# 02-USER_IO.net
KiCad netlist of a schematic drawn in Altium Designer
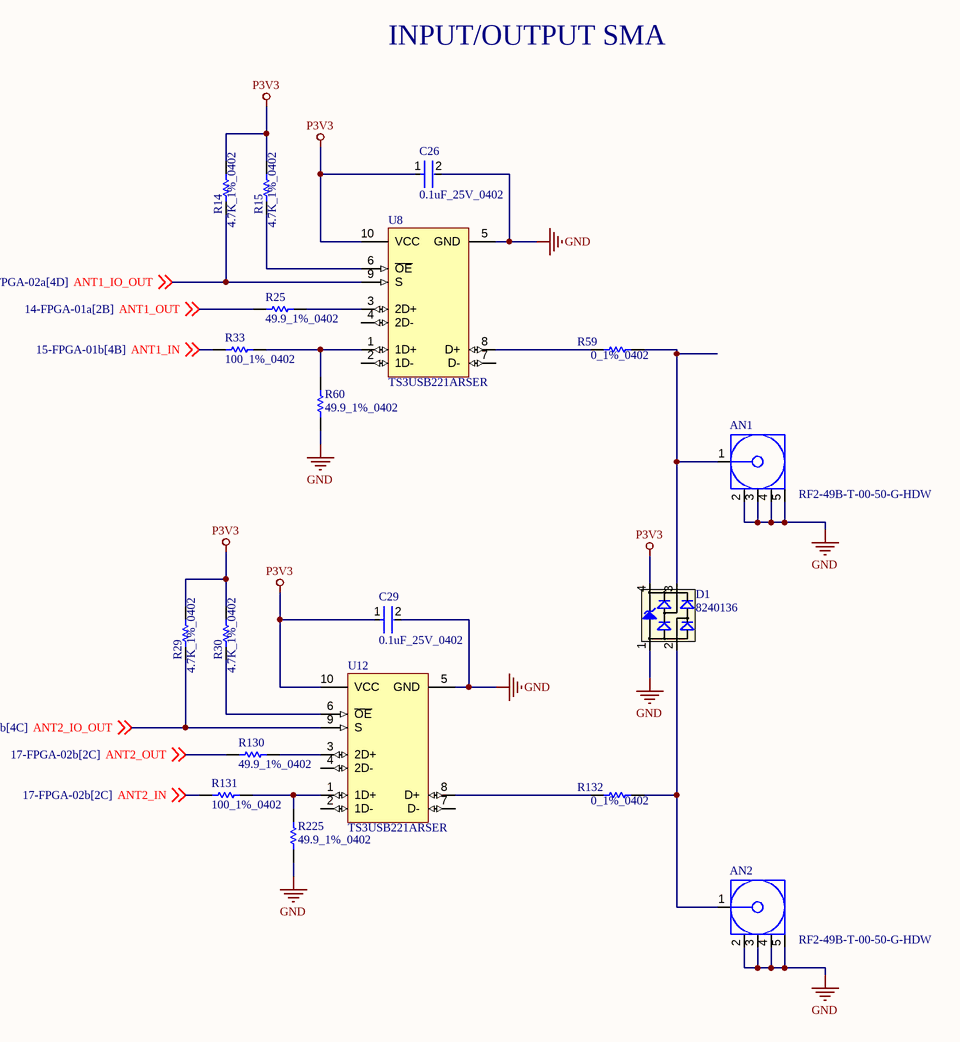
[diagram p0: 02-USER_IO.SchDoc]

(export (version "E")
  (design (tool "Eeschema 10.0.6"))
  (components
    (comp (ref "AN1")
      (value "RF2-49B-T-00-50-G-HDW")
      (footprint "AMPH-901-143-6RFX_V")
      (description "Coaxial connector, 50 Ohm, -65 to 165 degC, 5-Pin THD, RoHS, Bulk")
      (fields (field (name "MANUFACTURER") "Amphenol"))
      (libsource (lib "Altium Content Vault") (part "CN-S-4F-RF5"))
    )
    (comp (ref "AN2")
      (value "RF2-49B-T-00-50-G-HDW")
      (footprint "AMPH-901-143-6RFX_V")
      (description "Coaxial connector, 50 Ohm, -65 to 165 degC, 5-Pin THD, RoHS, Bulk")
      (fields (field (name "MANUFACTURER") "Amphenol"))
      (libsource (lib "Altium Content Vault") (part "CN-S-4F-RF5"))
    )
    (comp (ref "C26")
      (value "0.1uF_25V_0402")
      (footprint "FP-0402-L_1_0_1-W_0_5_0_1-IPC_C")
      (description "General Purpose Ceramic Capacitor, 0402, 100nF, 10%, X7R, 15%, 25V")
      (fields (field (name "VOLTAGE") "25V") (field (name "TOLERANCE") "10%"))
      (libsource (lib "Altium Content Vault") (part "b4654b650e69147ec39a6b967a45e02"))
    )
    (comp (ref "C29")
      (value "0.1uF_25V_0402")
      (footprint "FP-0402-L_1_0_1-W_0_5_0_1-IPC_C")
      (description "General Purpose Ceramic Capacitor, 0402, 100nF, 10%, X7R, 15%, 25V")
      (fields (field (name "VOLTAGE") "25V") (field (name "TOLERANCE") "10%"))
      (libsource (lib "Altium Content Vault") (part "b4654b650e69147ec39a6b967a45e02"))
    )
    (comp (ref "D1")
      (value "8240136")
      (footprint "SOT143-4L")
      (description "TVS Diode WE-TVS-HS, VRWM=3.3V")
      (fields (field (name "MANUFACTURER") "Wuerth Elektronik"))
      (libsource (lib "Altium Content Vault") (part "WE-TVS-HS-4"))
    )
    (comp (ref "R14")
      (value "4.7K_1%_0402")
      (footprint "RESC1005X40X25NL10T10")
      (fields (field (name "MANUFACTURER") "Bourns") (field (name "PART NUMBER") "CR0402-FX-4701GLF"))
      (libsource (lib "Altium Content Vault") (part "RES"))
    )
    (comp (ref "R15")
      (value "4.7K_1%_0402")
      (footprint "RESC1005X40X25NL10T10")
      (fields (field (name "MANUFACTURER") "Bourns") (field (name "PART NUMBER") "CR0402-FX-4701GLF"))
      (libsource (lib "Altium Content Vault") (part "RES"))
    )
    (comp (ref "R25")
      (value "49.9_1%_0402")
      (footprint "RESC1005X40X25NL10T10")
      (fields (field (name "PART NUMBER") "RK73H1ETTP49R9F") (field (name "MANUFACTURER") "KOA Speer"))
      (libsource (lib "Altium Content Vault") (part "RES"))
    )
    (comp (ref "R29")
      (value "4.7K_1%_0402")
      (footprint "RESC1005X40X25NL10T10")
      (fields (field (name "MANUFACTURER") "Bourns") (field (name "PART NUMBER") "CR0402-FX-4701GLF"))
      (libsource (lib "Altium Content Vault") (part "RES"))
    )
    (comp (ref "R30")
      (value "4.7K_1%_0402")
      (footprint "RESC1005X40X25NL10T10")
      (fields (field (name "MANUFACTURER") "Bourns") (field (name "PART NUMBER") "CR0402-FX-4701GLF"))
      (libsource (lib "Altium Content Vault") (part "RES"))
    )
    (comp (ref "R33")
      (value "100_1%_0402")
      (footprint "RESC1005X40X25NL05T10")
      (fields (field (name "MANUFACTURER") "Yageo") (field (name "PART NUMBER") "RC0402FR-13100RL"))
      (libsource (lib "Altium Content Vault") (part "RES"))
    )
    (comp (ref "R59")
      (value "0_1%_0402")
      (footprint "RESC1005X40X25LL05T05")
      (description "Chip Resistor, 0 Ohm, 0.1 W, -55 to 155 degC, 0402 (1005 Metric), RoHS, Tape and Reel")
      (fields (field (name "MANUFACTURER") "Panasonic") (field (name "TOLERANCE") "5%"))
      (libsource (lib "Altium Content Vault") (part "RES-2"))
    )
    (comp (ref "R60")
      (value "49.9_1%_0402")
      (footprint "RESC1005X40X25NL10T10")
      (fields (field (name "PART NUMBER") "RK73H1ETTP49R9F") (field (name "MANUFACTURER") "KOA Speer"))
      (libsource (lib "Altium Content Vault") (part "RES"))
    )
    (comp (ref "R130")
      (value "49.9_1%_0402")
      (footprint "RESC1005X40X25NL10T10")
      (fields (field (name "PART NUMBER") "RK73H1ETTP49R9F") (field (name "MANUFACTURER") "KOA Speer"))
      (libsource (lib "Altium Content Vault") (part "RES"))
    )
    (comp (ref "R131")
      (value "100_1%_0402")
      (footprint "RESC1005X40X25NL05T10")
      (fields (field (name "MANUFACTURER") "Yageo") (field (name "PART NUMBER") "RC0402FR-13100RL"))
      (libsource (lib "Altium Content Vault") (part "RES"))
    )
    (comp (ref "R132")
      (value "0_1%_0402")
      (footprint "RESC1005X40X25LL05T05")
      (description "Chip Resistor, 0 Ohm, 0.1 W, -55 to 155 degC, 0402 (1005 Metric), RoHS, Tape and Reel")
      (fields (field (name "MANUFACTURER") "Panasonic") (field (name "TOLERANCE") "5%"))
      (libsource (lib "Altium Content Vault") (part "RES-2"))
    )
    (comp (ref "R225")
      (value "49.9_1%_0402")
      (footprint "RESC1005X40X25NL10T10")
      (fields (field (name "PART NUMBER") "RK73H1ETTP49R9F") (field (name "MANUFACTURER") "KOA Speer"))
      (libsource (lib "Altium Content Vault") (part "RES"))
    )
    (comp (ref "U8")
      (value "TS3USB221ARSER")
      (footprint "RSE0010A_V")
      (fields (field (name "MANUFACTURER") "Texas Instruments"))
      (libsource (lib "Altium Content Vault") (part "TI-TS3USB221A-UQFN_RSE-10"))
    )
    (comp (ref "U12")
      (value "TS3USB221ARSER")
      (footprint "RSE0010A_V")
      (fields (field (name "MANUFACTURER") "Texas Instruments"))
      (libsource (lib "Altium Content Vault") (part "TI-TS3USB221A-UQFN_RSE-10"))
    )
  )
  (nets
    (net (code "1") (name "ANT1_IN") (class "Default")
      (node (ref "R33") (pin "1") (pinfunction "1_1") (pintype "passive"))
    )
    (net (code "2") (name "ANT1_IO_OUT") (class "Default")
      (node (ref "R14") (pin "2") (pinfunction "2_2") (pintype "passive"))
      (node (ref "U8") (pin "9") (pinfunction "S_9") (pintype "input"))
    )
    (net (code "3") (name "ANT1_OUT") (class "Default")
      (node (ref "R25") (pin "1") (pinfunction "1_1") (pintype "passive"))
    )
    (net (code "4") (name "ANT2_IN") (class "Default")
      (node (ref "R131") (pin "1") (pinfunction "1_1") (pintype "passive"))
    )
    (net (code "5") (name "ANT2_IO_OUT") (class "Default")
      (node (ref "R29") (pin "2") (pinfunction "2_2") (pintype "passive"))
      (node (ref "U12") (pin "9") (pinfunction "S_9") (pintype "input"))
    )
    (net (code "6") (name "ANT2_OUT") (class "Default")
      (node (ref "R130") (pin "1") (pinfunction "1_1") (pintype "passive"))
    )
    (net (code "7") (name "GND") (class "Default")
      (node (ref "AN1") (pin "2") (pinfunction "2_2") (pintype "passive"))
      (node (ref "AN1") (pin "3") (pinfunction "3_3") (pintype "passive"))
      (node (ref "AN1") (pin "4") (pinfunction "4_4") (pintype "passive"))
      (node (ref "AN1") (pin "5") (pinfunction "5_5") (pintype "passive"))
      (node (ref "AN2") (pin "2") (pinfunction "2_2") (pintype "passive"))
      (node (ref "AN2") (pin "3") (pinfunction "3_3") (pintype "passive"))
      (node (ref "AN2") (pin "4") (pinfunction "4_4") (pintype "passive"))
      (node (ref "AN2") (pin "5") (pinfunction "5_5") (pintype "passive"))
      (node (ref "C26") (pin "2") (pinfunction "2_2") (pintype "passive"))
      (node (ref "C29") (pin "2") (pinfunction "2_2") (pintype "passive"))
      (node (ref "D1") (pin "1") (pinfunction "GND_1") (pintype "passive"))
      (node (ref "R225") (pin "1") (pinfunction "1_1") (pintype "passive"))
      (node (ref "R60") (pin "1") (pinfunction "1_1") (pintype "passive"))
      (node (ref "U12") (pin "5") (pinfunction "GND_5") (pintype "power_in"))
      (node (ref "U8") (pin "5") (pinfunction "GND_5") (pintype "power_in"))
    )
    (net (code "8") (name "Net-(D1-I{slash}O1)") (class "Default")
      (node (ref "AN2") (pin "1") (pinfunction "1_1") (pintype "passive"))
      (node (ref "D1") (pin "2") (pinfunction "I/O1_2") (pintype "passive"))
      (node (ref "R132") (pin "2") (pinfunction "2_2") (pintype "passive"))
    )
    (net (code "9") (name "Net-(D1-I{slash}O2)") (class "Default")
      (node (ref "AN1") (pin "1") (pinfunction "1_1") (pintype "passive"))
      (node (ref "D1") (pin "3") (pinfunction "I/O2_3") (pintype "passive"))
      (node (ref "R59") (pin "2") (pinfunction "2_2") (pintype "passive"))
    )
    (net (code "10") (name "Net-(U8-1D+)") (class "Default")
      (node (ref "R33") (pin "2") (pinfunction "2_2") (pintype "passive"))
      (node (ref "R60") (pin "2") (pinfunction "2_2") (pintype "passive"))
      (node (ref "U8") (pin "1") (pinfunction "1D+_1") (pintype "bidirectional"))
    )
    (net (code "11") (name "Net-(U8-2D+)") (class "Default")
      (node (ref "R25") (pin "2") (pinfunction "2_2") (pintype "passive"))
      (node (ref "U8") (pin "3") (pinfunction "2D+_3") (pintype "bidirectional"))
    )
    (net (code "12") (name "Net-(U8-D+)") (class "Default")
      (node (ref "R59") (pin "1") (pinfunction "1_1") (pintype "passive"))
      (node (ref "U8") (pin "8") (pinfunction "D+_8") (pintype "bidirectional"))
    )
    (net (code "13") (name "Net-(U8-~{OE})") (class "Default")
      (node (ref "R15") (pin "2") (pinfunction "2_2") (pintype "passive"))
      (node (ref "U8") (pin "6") (pinfunction "~{OE}_6") (pintype "input"))
    )
    (net (code "14") (name "Net-(U12-1D+)") (class "Default")
      (node (ref "R131") (pin "2") (pinfunction "2_2") (pintype "passive"))
      (node (ref "R225") (pin "2") (pinfunction "2_2") (pintype "passive"))
      (node (ref "U12") (pin "1") (pinfunction "1D+_1") (pintype "bidirectional"))
    )
    (net (code "15") (name "Net-(U12-2D+)") (class "Default")
      (node (ref "R130") (pin "2") (pinfunction "2_2") (pintype "passive"))
      (node (ref "U12") (pin "3") (pinfunction "2D+_3") (pintype "bidirectional"))
    )
    (net (code "16") (name "Net-(U12-D+)") (class "Default")
      (node (ref "R132") (pin "1") (pinfunction "1_1") (pintype "passive"))
      (node (ref "U12") (pin "8") (pinfunction "D+_8") (pintype "bidirectional"))
    )
    (net (code "17") (name "Net-(U12-~{OE})") (class "Default")
      (node (ref "R30") (pin "2") (pinfunction "2_2") (pintype "passive"))
      (node (ref "U12") (pin "6") (pinfunction "~{OE}_6") (pintype "input"))
    )
    (net (code "18") (name "P3V3") (class "Default")
      (node (ref "C26") (pin "1") (pinfunction "1_1") (pintype "passive"))
      (node (ref "C29") (pin "1") (pinfunction "1_1") (pintype "passive"))
      (node (ref "D1") (pin "4") (pinfunction "VDD_4") (pintype "passive"))
      (node (ref "R14") (pin "1") (pinfunction "1_1") (pintype "passive"))
      (node (ref "R15") (pin "1") (pinfunction "1_1") (pintype "passive"))
      (node (ref "R29") (pin "1") (pinfunction "1_1") (pintype "passive"))
      (node (ref "R30") (pin "1") (pinfunction "1_1") (pintype "passive"))
      (node (ref "U12") (pin "10") (pinfunction "VCC_10") (pintype "power_in"))
      (node (ref "U8") (pin "10") (pinfunction "VCC_10") (pintype "power_in"))
    )
    (net (code "19") (name "unconnected-(U8-1D--Pad2)") (class "Default")
      (node (ref "U8") (pin "2") (pinfunction "1D-_2") (pintype "bidirectional"))
    )
    (net (code "20") (name "unconnected-(U8-2D--Pad4)") (class "Default")
      (node (ref "U8") (pin "4") (pinfunction "2D-_4") (pintype "bidirectional"))
    )
    (net (code "21") (name "unconnected-(U8-D--Pad7)") (class "Default")
      (node (ref "U8") (pin "7") (pinfunction "D-_7") (pintype "bidirectional"))
    )
    (net (code "22") (name "unconnected-(U12-1D--Pad2)") (class "Default")
      (node (ref "U12") (pin "2") (pinfunction "1D-_2") (pintype "bidirectional"))
    )
    (net (code "23") (name "unconnected-(U12-2D--Pad4)") (class "Default")
      (node (ref "U12") (pin "4") (pinfunction "2D-_4") (pintype "bidirectional"))
    )
    (net (code "24") (name "unconnected-(U12-D--Pad7)") (class "Default")
      (node (ref "U12") (pin "7") (pinfunction "D-_7") (pintype "bidirectional"))
    )
  )
)
